# SERVOS-1.net
KiCad netlist of a schematic drawn in EAGLE
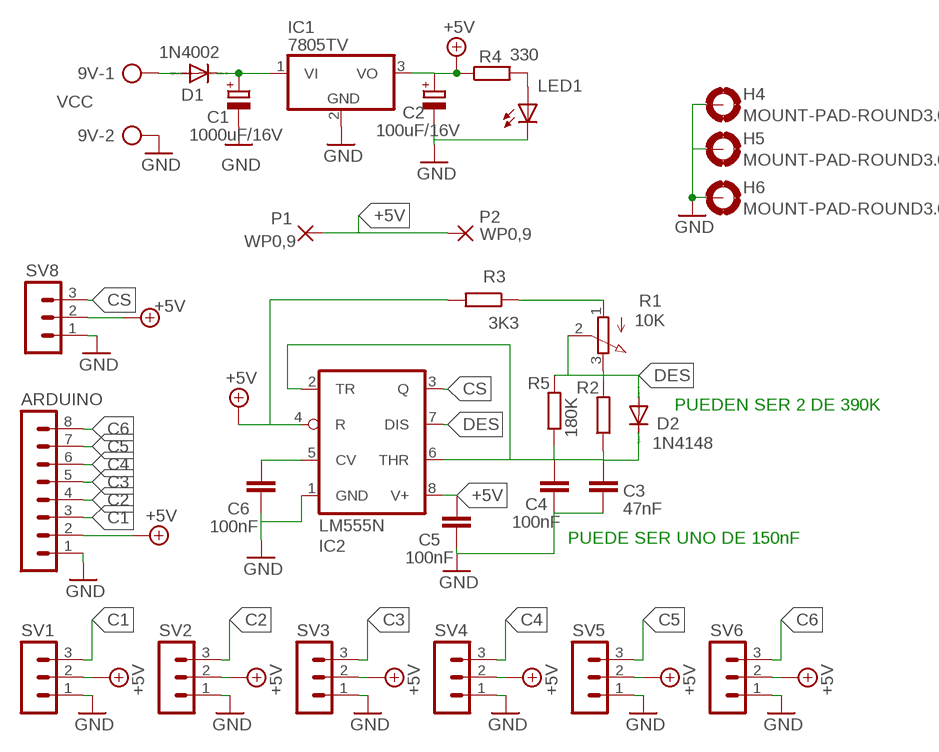
[diagram p0: schematic, sheet 1]

(export (version "E")
  (design (tool "Eeschema 10.0.6"))
  (components
    (comp (ref "9V")
      (value "VCC")
      (footprint "eagle-import:AK500_2")
      (libsource (lib "eagle-import") (part "AK500/2"))
    )
    (comp (ref "ARDUINO")
      (value "MA08-1")
      (footprint "eagle-import:MA08-1")
      (libsource (lib "eagle-import") (part "MA08-1"))
    )
    (comp (ref "C1")
      (value "1000uF/16V")
      (footprint "eagle-import:E2,5-7")
      (libsource (lib "eagle-import") (part "CPOL-EUE2.5-7"))
    )
    (comp (ref "C2")
      (value "100uF/16V")
      (footprint "eagle-import:E2,5-5")
      (libsource (lib "eagle-import") (part "CPOL-EUE2.5-5"))
    )
    (comp (ref "C3")
      (value "47nF")
      (footprint "eagle-import:C050-025X075")
      (libsource (lib "eagle-import") (part "C-EU050-025X075"))
    )
    (comp (ref "C4")
      (value "100nF")
      (footprint "eagle-import:C050-025X075")
      (libsource (lib "eagle-import") (part "C-EU050-025X075"))
    )
    (comp (ref "C5")
      (value "100nF")
      (footprint "eagle-import:C050-025X075")
      (libsource (lib "eagle-import") (part "C-EU050-025X075"))
    )
    (comp (ref "C6")
      (value "100nF")
      (footprint "eagle-import:C050-025X075")
      (libsource (lib "eagle-import") (part "C-EU050-025X075"))
    )
    (comp (ref "D1")
      (value "1N4002")
      (footprint "eagle-import:DO35-7")
      (libsource (lib "eagle-import") (part "1N4148DO35-7"))
    )
    (comp (ref "D2")
      (value "1N4148")
      (footprint "eagle-import:DO35-7")
      (libsource (lib "eagle-import") (part "1N4148DO35-7"))
    )
    (comp (ref "H4")
      (value "MOUNT-PAD-ROUND3.0")
      (footprint "eagle-import:3,0-PAD")
      (libsource (lib "eagle-import") (part "MOUNT-PAD-ROUND3.0"))
    )
    (comp (ref "H5")
      (value "MOUNT-PAD-ROUND3.0")
      (footprint "eagle-import:3,0-PAD")
      (libsource (lib "eagle-import") (part "MOUNT-PAD-ROUND3.0"))
    )
    (comp (ref "H6")
      (value "MOUNT-PAD-ROUND3.0")
      (footprint "eagle-import:3,0-PAD")
      (libsource (lib "eagle-import") (part "MOUNT-PAD-ROUND3.0"))
    )
    (comp (ref "IC1")
      (value "7805TV")
      (footprint "eagle-import:TO220V")
      (libsource (lib "eagle-import") (part "78TV05"))
    )
    (comp (ref "IC2")
      (value "LM555N")
      (footprint "eagle-import:DIL08")
      (libsource (lib "eagle-import") (part "555NLM"))
    )
    (comp (ref "LED1")
      (value "LED3MM")
      (footprint "eagle-import:LED3MM")
      (libsource (lib "eagle-import") (part "LED3MM"))
    )
    (comp (ref "P1")
      (value "WP0,9")
      (footprint "eagle-import:1,6_0,9")
      (libsource (lib "eagle-import") (part "WIREPAD1,6/0,9"))
    )
    (comp (ref "P2")
      (value "WP0,9")
      (footprint "eagle-import:1,6_0,9")
      (libsource (lib "eagle-import") (part "WIREPAD1,6/0,9"))
    )
    (comp (ref "R1")
      (value "10K")
      (footprint "eagle-import:3RP_1610N")
      (libsource (lib "eagle-import") (part "3RP/1610N"))
    )
    (comp (ref "R2")
      (value "R-EU_0207/10")
      (footprint "eagle-import:0207_10")
      (libsource (lib "eagle-import") (part "R-EU_0207/10"))
    )
    (comp (ref "R3")
      (value "3K3")
      (footprint "eagle-import:0207_10")
      (libsource (lib "eagle-import") (part "R-EU_0207/10"))
    )
    (comp (ref "R4")
      (value "330")
      (footprint "eagle-import:0207_10")
      (libsource (lib "eagle-import") (part "R-EU_0207/10"))
    )
    (comp (ref "R5")
      (value "180K")
      (footprint "eagle-import:0207_10")
      (libsource (lib "eagle-import") (part "R-EU_0207/10"))
    )
    (comp (ref "SV1")
      (value "MA03-1")
      (footprint "eagle-import:MA03-1")
      (libsource (lib "eagle-import") (part "MA03-1"))
    )
    (comp (ref "SV2")
      (value "MA03-1")
      (footprint "eagle-import:MA03-1")
      (libsource (lib "eagle-import") (part "MA03-1"))
    )
    (comp (ref "SV3")
      (value "MA03-1")
      (footprint "eagle-import:MA03-1")
      (libsource (lib "eagle-import") (part "MA03-1"))
    )
    (comp (ref "SV4")
      (value "MA03-1")
      (footprint "eagle-import:MA03-1")
      (libsource (lib "eagle-import") (part "MA03-1"))
    )
    (comp (ref "SV5")
      (value "MA03-1")
      (footprint "eagle-import:MA03-1")
      (libsource (lib "eagle-import") (part "MA03-1"))
    )
    (comp (ref "SV6")
      (value "MA03-1")
      (footprint "eagle-import:MA03-1")
      (libsource (lib "eagle-import") (part "MA03-1"))
    )
    (comp (ref "SV8")
      (value "MA03-1")
      (footprint "eagle-import:MA03-1")
      (libsource (lib "eagle-import") (part "MA03-1"))
    )
  )
  (nets
    (net (code "1") (name "+5V") (class "Default")
      (node (ref "ARDUINO") (pin "2") (pinfunction "2_2") (pintype "passive"))
      (node (ref "C2") (pin "+") (pinfunction "+_+") (pintype "passive"))
      (node (ref "C5") (pin "1") (pinfunction "1_1") (pintype "passive"))
      (node (ref "IC1") (pin "3") (pinfunction "VO_3") (pintype "passive"))
      (node (ref "IC2") (pin "4") (pinfunction "R_4") (pintype "input"))
      (node (ref "IC2") (pin "8") (pinfunction "V+_8") (pintype "power_in"))
      (node (ref "P1") (pin "1") (pinfunction "P_1") (pintype "passive"))
      (node (ref "P2") (pin "1") (pinfunction "P_1") (pintype "passive"))
      (node (ref "R3") (pin "2") (pinfunction "2_2") (pintype "passive"))
      (node (ref "R4") (pin "1") (pinfunction "1_1") (pintype "passive"))
      (node (ref "SV1") (pin "2") (pinfunction "2_2") (pintype "passive"))
      (node (ref "SV2") (pin "2") (pinfunction "2_2") (pintype "passive"))
      (node (ref "SV3") (pin "2") (pinfunction "2_2") (pintype "passive"))
      (node (ref "SV4") (pin "2") (pinfunction "2_2") (pintype "passive"))
      (node (ref "SV5") (pin "2") (pinfunction "2_2") (pintype "passive"))
      (node (ref "SV6") (pin "2") (pinfunction "2_2") (pintype "passive"))
      (node (ref "SV8") (pin "2") (pinfunction "2_2") (pintype "passive"))
    )
    (net (code "2") (name "C1") (class "Default")
      (node (ref "ARDUINO") (pin "3") (pinfunction "3_3") (pintype "passive"))
      (node (ref "SV1") (pin "3") (pinfunction "3_3") (pintype "passive"))
    )
    (net (code "3") (name "C2") (class "Default")
      (node (ref "ARDUINO") (pin "4") (pinfunction "4_4") (pintype "passive"))
      (node (ref "SV2") (pin "3") (pinfunction "3_3") (pintype "passive"))
    )
    (net (code "4") (name "C3") (class "Default")
      (node (ref "ARDUINO") (pin "5") (pinfunction "5_5") (pintype "passive"))
      (node (ref "SV3") (pin "3") (pinfunction "3_3") (pintype "passive"))
    )
    (net (code "5") (name "C4") (class "Default")
      (node (ref "ARDUINO") (pin "6") (pinfunction "6_6") (pintype "passive"))
      (node (ref "SV4") (pin "3") (pinfunction "3_3") (pintype "passive"))
    )
    (net (code "6") (name "C5") (class "Default")
      (node (ref "ARDUINO") (pin "7") (pinfunction "7_7") (pintype "passive"))
      (node (ref "SV5") (pin "3") (pinfunction "3_3") (pintype "passive"))
    )
    (net (code "7") (name "C6") (class "Default")
      (node (ref "ARDUINO") (pin "8") (pinfunction "8_8") (pintype "passive"))
      (node (ref "SV6") (pin "3") (pinfunction "3_3") (pintype "passive"))
    )
    (net (code "8") (name "CS") (class "Default")
      (node (ref "IC2") (pin "3") (pinfunction "Q_3") (pintype "output"))
      (node (ref "SV8") (pin "3") (pinfunction "3_3") (pintype "passive"))
    )
    (net (code "9") (name "DES") (class "Default")
      (node (ref "D2") (pin "A") (pinfunction "A_A") (pintype "passive"))
      (node (ref "IC2") (pin "7") (pinfunction "DIS_7") (pintype "input"))
      (node (ref "R1") (pin "2") (pinfunction "S_2") (pintype "passive"))
      (node (ref "R1") (pin "3") (pinfunction "E_3") (pintype "passive"))
      (node (ref "R2") (pin "2") (pinfunction "2_2") (pintype "passive"))
      (node (ref "R5") (pin "2") (pinfunction "2_2") (pintype "passive"))
    )
    (net (code "10") (name "GND") (class "Default")
      (node (ref "9V") (pin "2") (pinfunction "KL_2") (pintype "passive"))
      (node (ref "ARDUINO") (pin "1") (pinfunction "1_1") (pintype "passive"))
      (node (ref "C1") (pin "-") (pinfunction "-_-") (pintype "passive"))
      (node (ref "C2") (pin "-") (pinfunction "-_-") (pintype "passive"))
      (node (ref "C3") (pin "2") (pinfunction "2_2") (pintype "passive"))
      (node (ref "C4") (pin "2") (pinfunction "2_2") (pintype "passive"))
      (node (ref "C5") (pin "2") (pinfunction "2_2") (pintype "passive"))
      (node (ref "C6") (pin "2") (pinfunction "2_2") (pintype "passive"))
      (node (ref "H4") (pin "B3,0") (pinfunction "MOUNT_B3,0") (pintype "passive"))
      (node (ref "H5") (pin "B3,0") (pinfunction "MOUNT_B3,0") (pintype "passive"))
      (node (ref "H6") (pin "B3,0") (pinfunction "MOUNT_B3,0") (pintype "passive"))
      (node (ref "IC1") (pin "2") (pinfunction "GND_2") (pintype "passive"))
      (node (ref "IC2") (pin "1") (pinfunction "GND_1") (pintype "power_in"))
      (node (ref "LED1") (pin "K") (pinfunction "C_K") (pintype "passive"))
      (node (ref "SV1") (pin "1") (pinfunction "1_1") (pintype "passive"))
      (node (ref "SV2") (pin "1") (pinfunction "1_1") (pintype "passive"))
      (node (ref "SV3") (pin "1") (pinfunction "1_1") (pintype "passive"))
      (node (ref "SV4") (pin "1") (pinfunction "1_1") (pintype "passive"))
      (node (ref "SV5") (pin "1") (pinfunction "1_1") (pintype "passive"))
      (node (ref "SV6") (pin "1") (pinfunction "1_1") (pintype "passive"))
      (node (ref "SV8") (pin "1") (pinfunction "1_1") (pintype "passive"))
    )
    (net (code "11") (name "Net-(9VA-KL)") (class "Default")
      (node (ref "9V") (pin "1") (pinfunction "KL_1") (pintype "passive"))
      (node (ref "D1") (pin "A") (pinfunction "A_A") (pintype "passive"))
    )
    (net (code "12") (name "Net-(IC1-VI)") (class "Default")
      (node (ref "C1") (pin "+") (pinfunction "+_+") (pintype "passive"))
      (node (ref "D1") (pin "C") (pinfunction "C_C") (pintype "passive"))
      (node (ref "IC1") (pin "1") (pinfunction "VI_1") (pintype "input"))
    )
    (net (code "13") (name "Net-(IC2-CV)") (class "Default")
      (node (ref "C6") (pin "1") (pinfunction "1_1") (pintype "passive"))
      (node (ref "IC2") (pin "5") (pinfunction "CV_5") (pintype "input"))
    )
    (net (code "14") (name "Net-(IC2-THR)") (class "Default")
      (node (ref "C3") (pin "1") (pinfunction "1_1") (pintype "passive"))
      (node (ref "C4") (pin "1") (pinfunction "1_1") (pintype "passive"))
      (node (ref "D2") (pin "C") (pinfunction "C_C") (pintype "passive"))
      (node (ref "IC2") (pin "2") (pinfunction "TR_2") (pintype "input"))
      (node (ref "IC2") (pin "6") (pinfunction "THR_6") (pintype "input"))
      (node (ref "R2") (pin "1") (pinfunction "1_1") (pintype "passive"))
      (node (ref "R5") (pin "1") (pinfunction "1_1") (pintype "passive"))
    )
    (net (code "15") (name "Net-(LED1-PadA)") (class "Default")
      (node (ref "LED1") (pin "A") (pinfunction "A_A") (pintype "passive"))
      (node (ref "R4") (pin "2") (pinfunction "2_2") (pintype "passive"))
    )
    (net (code "16") (name "Net-(R1-A)") (class "Default")
      (node (ref "R1") (pin "1") (pinfunction "A_1") (pintype "passive"))
      (node (ref "R3") (pin "1") (pinfunction "1_1") (pintype "passive"))
    )
  )
)
